# Adafruit_AMG8833_FeatherWing.net
KiCad netlist of a schematic drawn in EAGLE
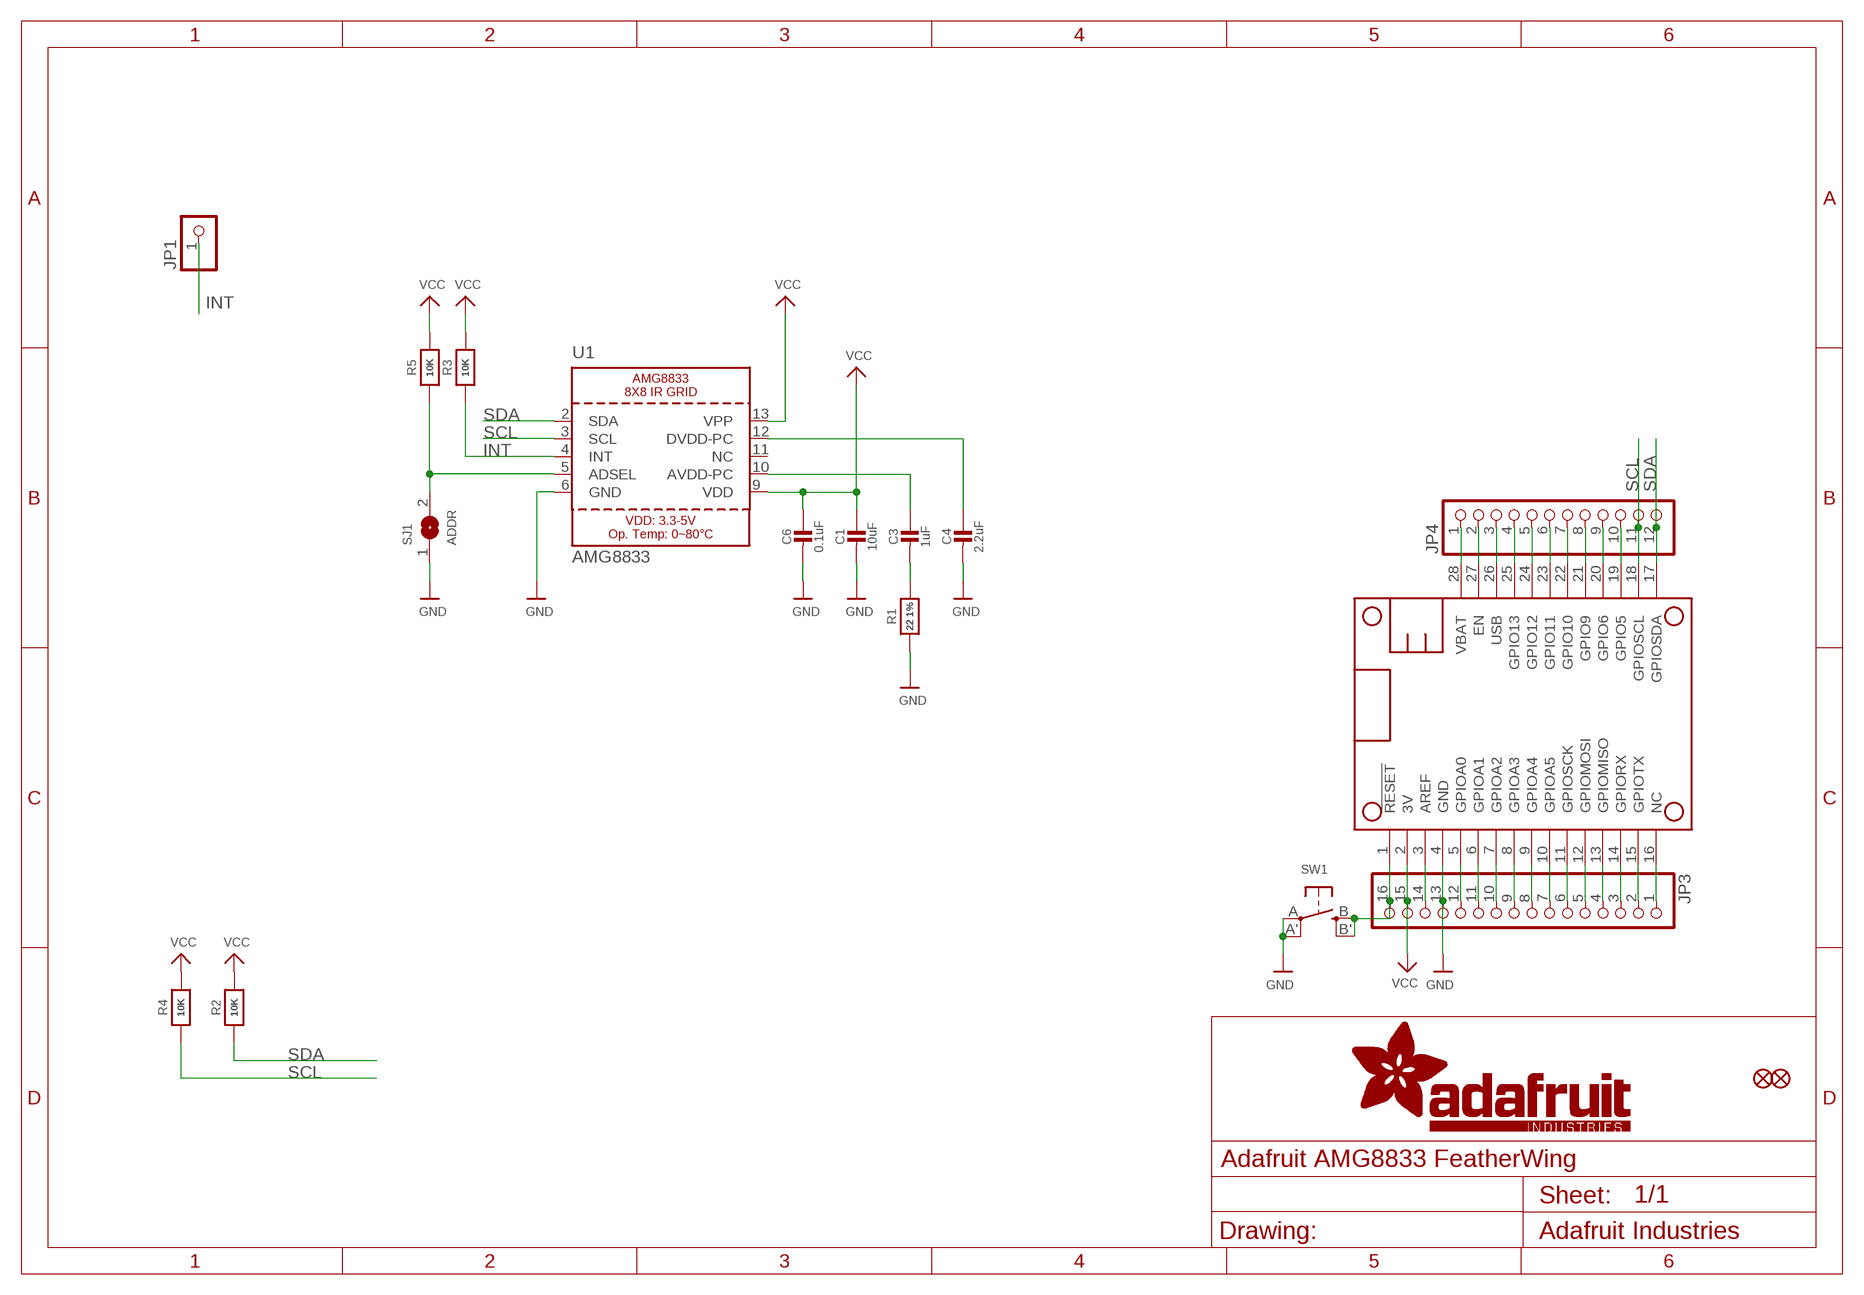
[diagram p0: schematic, sheet 1]

(export (version "E")
  (design (tool "Eeschema 10.0.6"))
  (components
    (comp (ref "C1")
      (value "10uF")
      (footprint "eagle-import:0805-NO")
      (libsource (lib "eagle-import") (part "CAP_CERAMIC0805-NOOUTLINE"))
    )
    (comp (ref "C3")
      (value "1uF")
      (footprint "eagle-import:0805-NO")
      (libsource (lib "eagle-import") (part "CAP_CERAMIC0805-NOOUTLINE"))
    )
    (comp (ref "C4")
      (value "2.2uF")
      (footprint "eagle-import:0805-NO")
      (libsource (lib "eagle-import") (part "CAP_CERAMIC0805-NOOUTLINE"))
    )
    (comp (ref "C6")
      (value "0.1uF")
      (footprint "eagle-import:0805-NO")
      (libsource (lib "eagle-import") (part "CAP_CERAMIC0805-NOOUTLINE"))
    )
    (comp (ref "FID1")
      (value "FIDUCIAL\"\"")
      (footprint "eagle-import:FIDUCIAL_1MM")
      (libsource (lib "eagle-import") (part "FIDUCIAL{dblquote}{dblquote}"))
    )
    (comp (ref "FID2")
      (value "FIDUCIAL\"\"")
      (footprint "eagle-import:FIDUCIAL_1MM")
      (libsource (lib "eagle-import") (part "FIDUCIAL{dblquote}{dblquote}"))
    )
    (comp (ref "JP1")
      (value "HEADER-1X1ROUND")
      (footprint "eagle-import:1X01_ROUND")
      (libsource (lib "eagle-import") (part "HEADER-1X1ROUND"))
    )
    (comp (ref "JP3")
      (value "HEADER-1X16ROUND")
      (footprint "eagle-import:1X16_ROUND")
      (libsource (lib "eagle-import") (part "HEADER-1X16ROUND"))
    )
    (comp (ref "JP4")
      (value "HEADER-1X12")
      (footprint "eagle-import:1X12_ROUND")
      (libsource (lib "eagle-import") (part "HEADER-1X12"))
    )
    (comp (ref "MS1")
      (value "FEATHERWING")
      (footprint "eagle-import:FEATHERWING")
      (libsource (lib "eagle-import") (part "FEATHERWING"))
    )
    (comp (ref "R1")
      (value "22 1%")
      (footprint "eagle-import:0805-NO")
      (libsource (lib "eagle-import") (part "RESISTOR0805_NOOUTLINE"))
    )
    (comp (ref "R2")
      (value "10K")
      (footprint "eagle-import:0805-NO")
      (libsource (lib "eagle-import") (part "RESISTOR0805_NOOUTLINE"))
    )
    (comp (ref "R3")
      (value "10K")
      (footprint "eagle-import:0805-NO")
      (libsource (lib "eagle-import") (part "RESISTOR0805_NOOUTLINE"))
    )
    (comp (ref "R4")
      (value "10K")
      (footprint "eagle-import:0805-NO")
      (libsource (lib "eagle-import") (part "RESISTOR0805_NOOUTLINE"))
    )
    (comp (ref "R5")
      (value "10K")
      (footprint "eagle-import:0805-NO")
      (libsource (lib "eagle-import") (part "RESISTOR0805_NOOUTLINE"))
    )
    (comp (ref "SJ1")
      (value "ADDR")
      (footprint "eagle-import:SOLDERJUMPER_ARROW_NOPASTE")
      (libsource (lib "eagle-import") (part "SOLDERJUMPER"))
    )
    (comp (ref "SW1")
      (value "SWITCH_TACT_SMT4.6X2.8")
      (footprint "eagle-import:BTN_KMR2_4.6X2.8")
      (libsource (lib "eagle-import") (part "SWITCH_TACT_SMT4.6X2.8"))
    )
    (comp (ref "U1")
      (value "AMG8833")
      (footprint "eagle-import:AMG8833")
      (libsource (lib "eagle-import") (part "AMG8833"))
    )
  )
  (nets
    (net (code "1") (name "/INT") (class "Default")
      (node (ref "JP1") (pin "1") (pinfunction "1_1") (pintype "passive"))
      (node (ref "R3") (pin "1") (pinfunction "1_1") (pintype "passive"))
      (node (ref "U1") (pin "4") (pinfunction "INT_4") (pintype "output"))
    )
    (net (code "2") (name "/SCL") (class "Default")
      (node (ref "JP4") (pin "11") (pinfunction "11_11") (pintype "passive"))
      (node (ref "MS1") (pin "18") (pinfunction "GPIOSCL_18") (pintype "bidirectional"))
      (node (ref "R4") (pin "1") (pinfunction "1_1") (pintype "passive"))
      (node (ref "U1") (pin "3") (pinfunction "SCL_3") (pintype "bidirectional"))
    )
    (net (code "3") (name "/SDA") (class "Default")
      (node (ref "JP4") (pin "12") (pinfunction "12_12") (pintype "passive"))
      (node (ref "MS1") (pin "17") (pinfunction "GPIOSDA_17") (pintype "bidirectional"))
      (node (ref "R2") (pin "1") (pinfunction "1_1") (pintype "passive"))
      (node (ref "U1") (pin "2") (pinfunction "SDA_2") (pintype "bidirectional"))
    )
    (net (code "4") (name "GND") (class "Default")
      (node (ref "C1") (pin "2") (pinfunction "2_2") (pintype "passive"))
      (node (ref "C4") (pin "2") (pinfunction "2_2") (pintype "passive"))
      (node (ref "C6") (pin "2") (pinfunction "2_2") (pintype "passive"))
      (node (ref "JP3") (pin "13") (pinfunction "13_13") (pintype "passive"))
      (node (ref "MS1") (pin "4") (pinfunction "GND_4") (pintype "power_in"))
      (node (ref "R1") (pin "1") (pinfunction "1_1") (pintype "passive"))
      (node (ref "SJ1") (pin "1") (pinfunction "1_1") (pintype "passive"))
      (node (ref "SW1") (pin "A") (pinfunction "P_A") (pintype "passive"))
      (node (ref "SW1") (pin "A'") (pinfunction "P1_A'") (pintype "passive"))
      (node (ref "U1") (pin "6") (pinfunction "GND_6") (pintype "power_in"))
    )
    (net (code "5") (name "Net-(C3-Pad2)") (class "Default")
      (node (ref "C3") (pin "2") (pinfunction "2_2") (pintype "passive"))
      (node (ref "R1") (pin "2") (pinfunction "2_2") (pintype "passive"))
    )
    (net (code "6") (name "Net-(MS1-AREF)") (class "Default")
      (node (ref "JP3") (pin "14") (pinfunction "14_14") (pintype "passive"))
      (node (ref "MS1") (pin "3") (pinfunction "AREF_3") (pintype "passive"))
    )
    (net (code "7") (name "Net-(MS1-EN)") (class "Default")
      (node (ref "JP4") (pin "2") (pinfunction "2_2") (pintype "passive"))
      (node (ref "MS1") (pin "27") (pinfunction "EN_27") (pintype "passive"))
    )
    (net (code "8") (name "Net-(MS1-GPIO5)") (class "Default")
      (node (ref "JP4") (pin "10") (pinfunction "10_10") (pintype "passive"))
      (node (ref "MS1") (pin "19") (pinfunction "GPIO5_19") (pintype "bidirectional"))
    )
    (net (code "9") (name "Net-(MS1-GPIO6)") (class "Default")
      (node (ref "JP4") (pin "9") (pinfunction "9_9") (pintype "passive"))
      (node (ref "MS1") (pin "20") (pinfunction "GPIO6_20") (pintype "bidirectional"))
    )
    (net (code "10") (name "Net-(MS1-GPIO9)") (class "Default")
      (node (ref "JP4") (pin "8") (pinfunction "8_8") (pintype "passive"))
      (node (ref "MS1") (pin "21") (pinfunction "GPIO9_21") (pintype "bidirectional"))
    )
    (net (code "11") (name "Net-(MS1-GPIO10)") (class "Default")
      (node (ref "JP4") (pin "7") (pinfunction "7_7") (pintype "passive"))
      (node (ref "MS1") (pin "22") (pinfunction "GPIO10_22") (pintype "bidirectional"))
    )
    (net (code "12") (name "Net-(MS1-GPIO11)") (class "Default")
      (node (ref "JP4") (pin "6") (pinfunction "6_6") (pintype "passive"))
      (node (ref "MS1") (pin "23") (pinfunction "GPIO11_23") (pintype "bidirectional"))
    )
    (net (code "13") (name "Net-(MS1-GPIO12)") (class "Default")
      (node (ref "JP4") (pin "5") (pinfunction "5_5") (pintype "passive"))
      (node (ref "MS1") (pin "24") (pinfunction "GPIO12_24") (pintype "bidirectional"))
    )
    (net (code "14") (name "Net-(MS1-GPIO13)") (class "Default")
      (node (ref "JP4") (pin "4") (pinfunction "4_4") (pintype "passive"))
      (node (ref "MS1") (pin "25") (pinfunction "GPIO13_25") (pintype "bidirectional"))
    )
    (net (code "15") (name "Net-(MS1-GPIOA0)") (class "Default")
      (node (ref "JP3") (pin "12") (pinfunction "12_12") (pintype "passive"))
      (node (ref "MS1") (pin "5") (pinfunction "GPIOA0_5") (pintype "bidirectional"))
    )
    (net (code "16") (name "Net-(MS1-GPIOA1)") (class "Default")
      (node (ref "JP3") (pin "11") (pinfunction "11_11") (pintype "passive"))
      (node (ref "MS1") (pin "6") (pinfunction "GPIOA1_6") (pintype "bidirectional"))
    )
    (net (code "17") (name "Net-(MS1-GPIOA2)") (class "Default")
      (node (ref "JP3") (pin "10") (pinfunction "10_10") (pintype "passive"))
      (node (ref "MS1") (pin "7") (pinfunction "GPIOA2_7") (pintype "bidirectional"))
    )
    (net (code "18") (name "Net-(MS1-GPIOA3)") (class "Default")
      (node (ref "JP3") (pin "9") (pinfunction "9_9") (pintype "passive"))
      (node (ref "MS1") (pin "8") (pinfunction "GPIOA3_8") (pintype "bidirectional"))
    )
    (net (code "19") (name "Net-(MS1-GPIOA4)") (class "Default")
      (node (ref "JP3") (pin "8") (pinfunction "8_8") (pintype "passive"))
      (node (ref "MS1") (pin "9") (pinfunction "GPIOA4_9") (pintype "bidirectional"))
    )
    (net (code "20") (name "Net-(MS1-GPIOA5)") (class "Default")
      (node (ref "JP3") (pin "7") (pinfunction "7_7") (pintype "passive"))
      (node (ref "MS1") (pin "10") (pinfunction "GPIOA5_10") (pintype "bidirectional"))
    )
    (net (code "21") (name "Net-(MS1-GPIOMISO)") (class "Default")
      (node (ref "JP3") (pin "4") (pinfunction "4_4") (pintype "passive"))
      (node (ref "MS1") (pin "13") (pinfunction "GPIOMISO_13") (pintype "bidirectional"))
    )
    (net (code "22") (name "Net-(MS1-GPIOMOSI)") (class "Default")
      (node (ref "JP3") (pin "5") (pinfunction "5_5") (pintype "passive"))
      (node (ref "MS1") (pin "12") (pinfunction "GPIOMOSI_12") (pintype "bidirectional"))
    )
    (net (code "23") (name "Net-(MS1-GPIORX)") (class "Default")
      (node (ref "JP3") (pin "3") (pinfunction "3_3") (pintype "passive"))
      (node (ref "MS1") (pin "14") (pinfunction "GPIORX_14") (pintype "bidirectional"))
    )
    (net (code "24") (name "Net-(MS1-GPIOSCK)") (class "Default")
      (node (ref "JP3") (pin "6") (pinfunction "6_6") (pintype "passive"))
      (node (ref "MS1") (pin "11") (pinfunction "GPIOSCK_11") (pintype "bidirectional"))
    )
    (net (code "25") (name "Net-(MS1-GPIOTX)") (class "Default")
      (node (ref "JP3") (pin "2") (pinfunction "2_2") (pintype "passive"))
      (node (ref "MS1") (pin "15") (pinfunction "GPIOTX_15") (pintype "bidirectional"))
    )
    (net (code "26") (name "Net-(MS1-NC)") (class "Default")
      (node (ref "JP3") (pin "1") (pinfunction "1_1") (pintype "passive"))
      (node (ref "MS1") (pin "16") (pinfunction "NC_16") (pintype "passive"))
    )
    (net (code "27") (name "Net-(MS1-USB)") (class "Default")
      (node (ref "JP4") (pin "3") (pinfunction "3_3") (pintype "passive"))
      (node (ref "MS1") (pin "26") (pinfunction "USB_26") (pintype "power_in"))
    )
    (net (code "28") (name "Net-(MS1-VBAT)") (class "Default")
      (node (ref "JP4") (pin "1") (pinfunction "1_1") (pintype "passive"))
      (node (ref "MS1") (pin "28") (pinfunction "VBAT_28") (pintype "power_in"))
    )
    (net (code "29") (name "Net-(MS1-~{RESET})") (class "Default")
      (node (ref "JP3") (pin "16") (pinfunction "16_16") (pintype "passive"))
      (node (ref "MS1") (pin "1") (pinfunction "~{RESET}_1") (pintype "input"))
      (node (ref "SW1") (pin "B") (pinfunction "S_B") (pintype "passive"))
      (node (ref "SW1") (pin "B'") (pinfunction "S1_B'") (pintype "passive"))
    )
    (net (code "30") (name "Net-(U1-ADSEL)") (class "Default")
      (node (ref "R5") (pin "1") (pinfunction "1_1") (pintype "passive"))
      (node (ref "SJ1") (pin "2") (pinfunction "2_2") (pintype "passive"))
      (node (ref "U1") (pin "5") (pinfunction "ADSEL_5") (pintype "input"))
    )
    (net (code "31") (name "Net-(U1-AVDD-PC)") (class "Default")
      (node (ref "C3") (pin "1") (pinfunction "1_1") (pintype "passive"))
      (node (ref "U1") (pin "10") (pinfunction "AVDD-PC_10") (pintype "power_in"))
    )
    (net (code "32") (name "Net-(U1-DVDD-PC)") (class "Default")
      (node (ref "C4") (pin "1") (pinfunction "1_1") (pintype "passive"))
      (node (ref "U1") (pin "12") (pinfunction "DVDD-PC_12") (pintype "power_in"))
    )
    (net (code "33") (name "VCC") (class "Default")
      (node (ref "C1") (pin "1") (pinfunction "1_1") (pintype "passive"))
      (node (ref "C6") (pin "1") (pinfunction "1_1") (pintype "passive"))
      (node (ref "JP3") (pin "15") (pinfunction "15_15") (pintype "passive"))
      (node (ref "MS1") (pin "2") (pinfunction "3V_2") (pintype "power_in"))
      (node (ref "R2") (pin "2") (pinfunction "2_2") (pintype "passive"))
      (node (ref "R3") (pin "2") (pinfunction "2_2") (pintype "passive"))
      (node (ref "R4") (pin "2") (pinfunction "2_2") (pintype "passive"))
      (node (ref "R5") (pin "2") (pinfunction "2_2") (pintype "passive"))
      (node (ref "U1") (pin "13") (pinfunction "VPP_13") (pintype "power_in"))
      (node (ref "U1") (pin "9") (pinfunction "VDD_9") (pintype "power_in"))
    )
    (net (code "34") (name "unconnected-(U1-NC-Pad11)") (class "Default")
      (node (ref "U1") (pin "11") (pinfunction "NC_11") (pintype "bidirectional"))
    )
  )
)
